# M466_and_M462B_Output_Amplifier.net
KiCad netlist of a schematic drawn in EAGLE
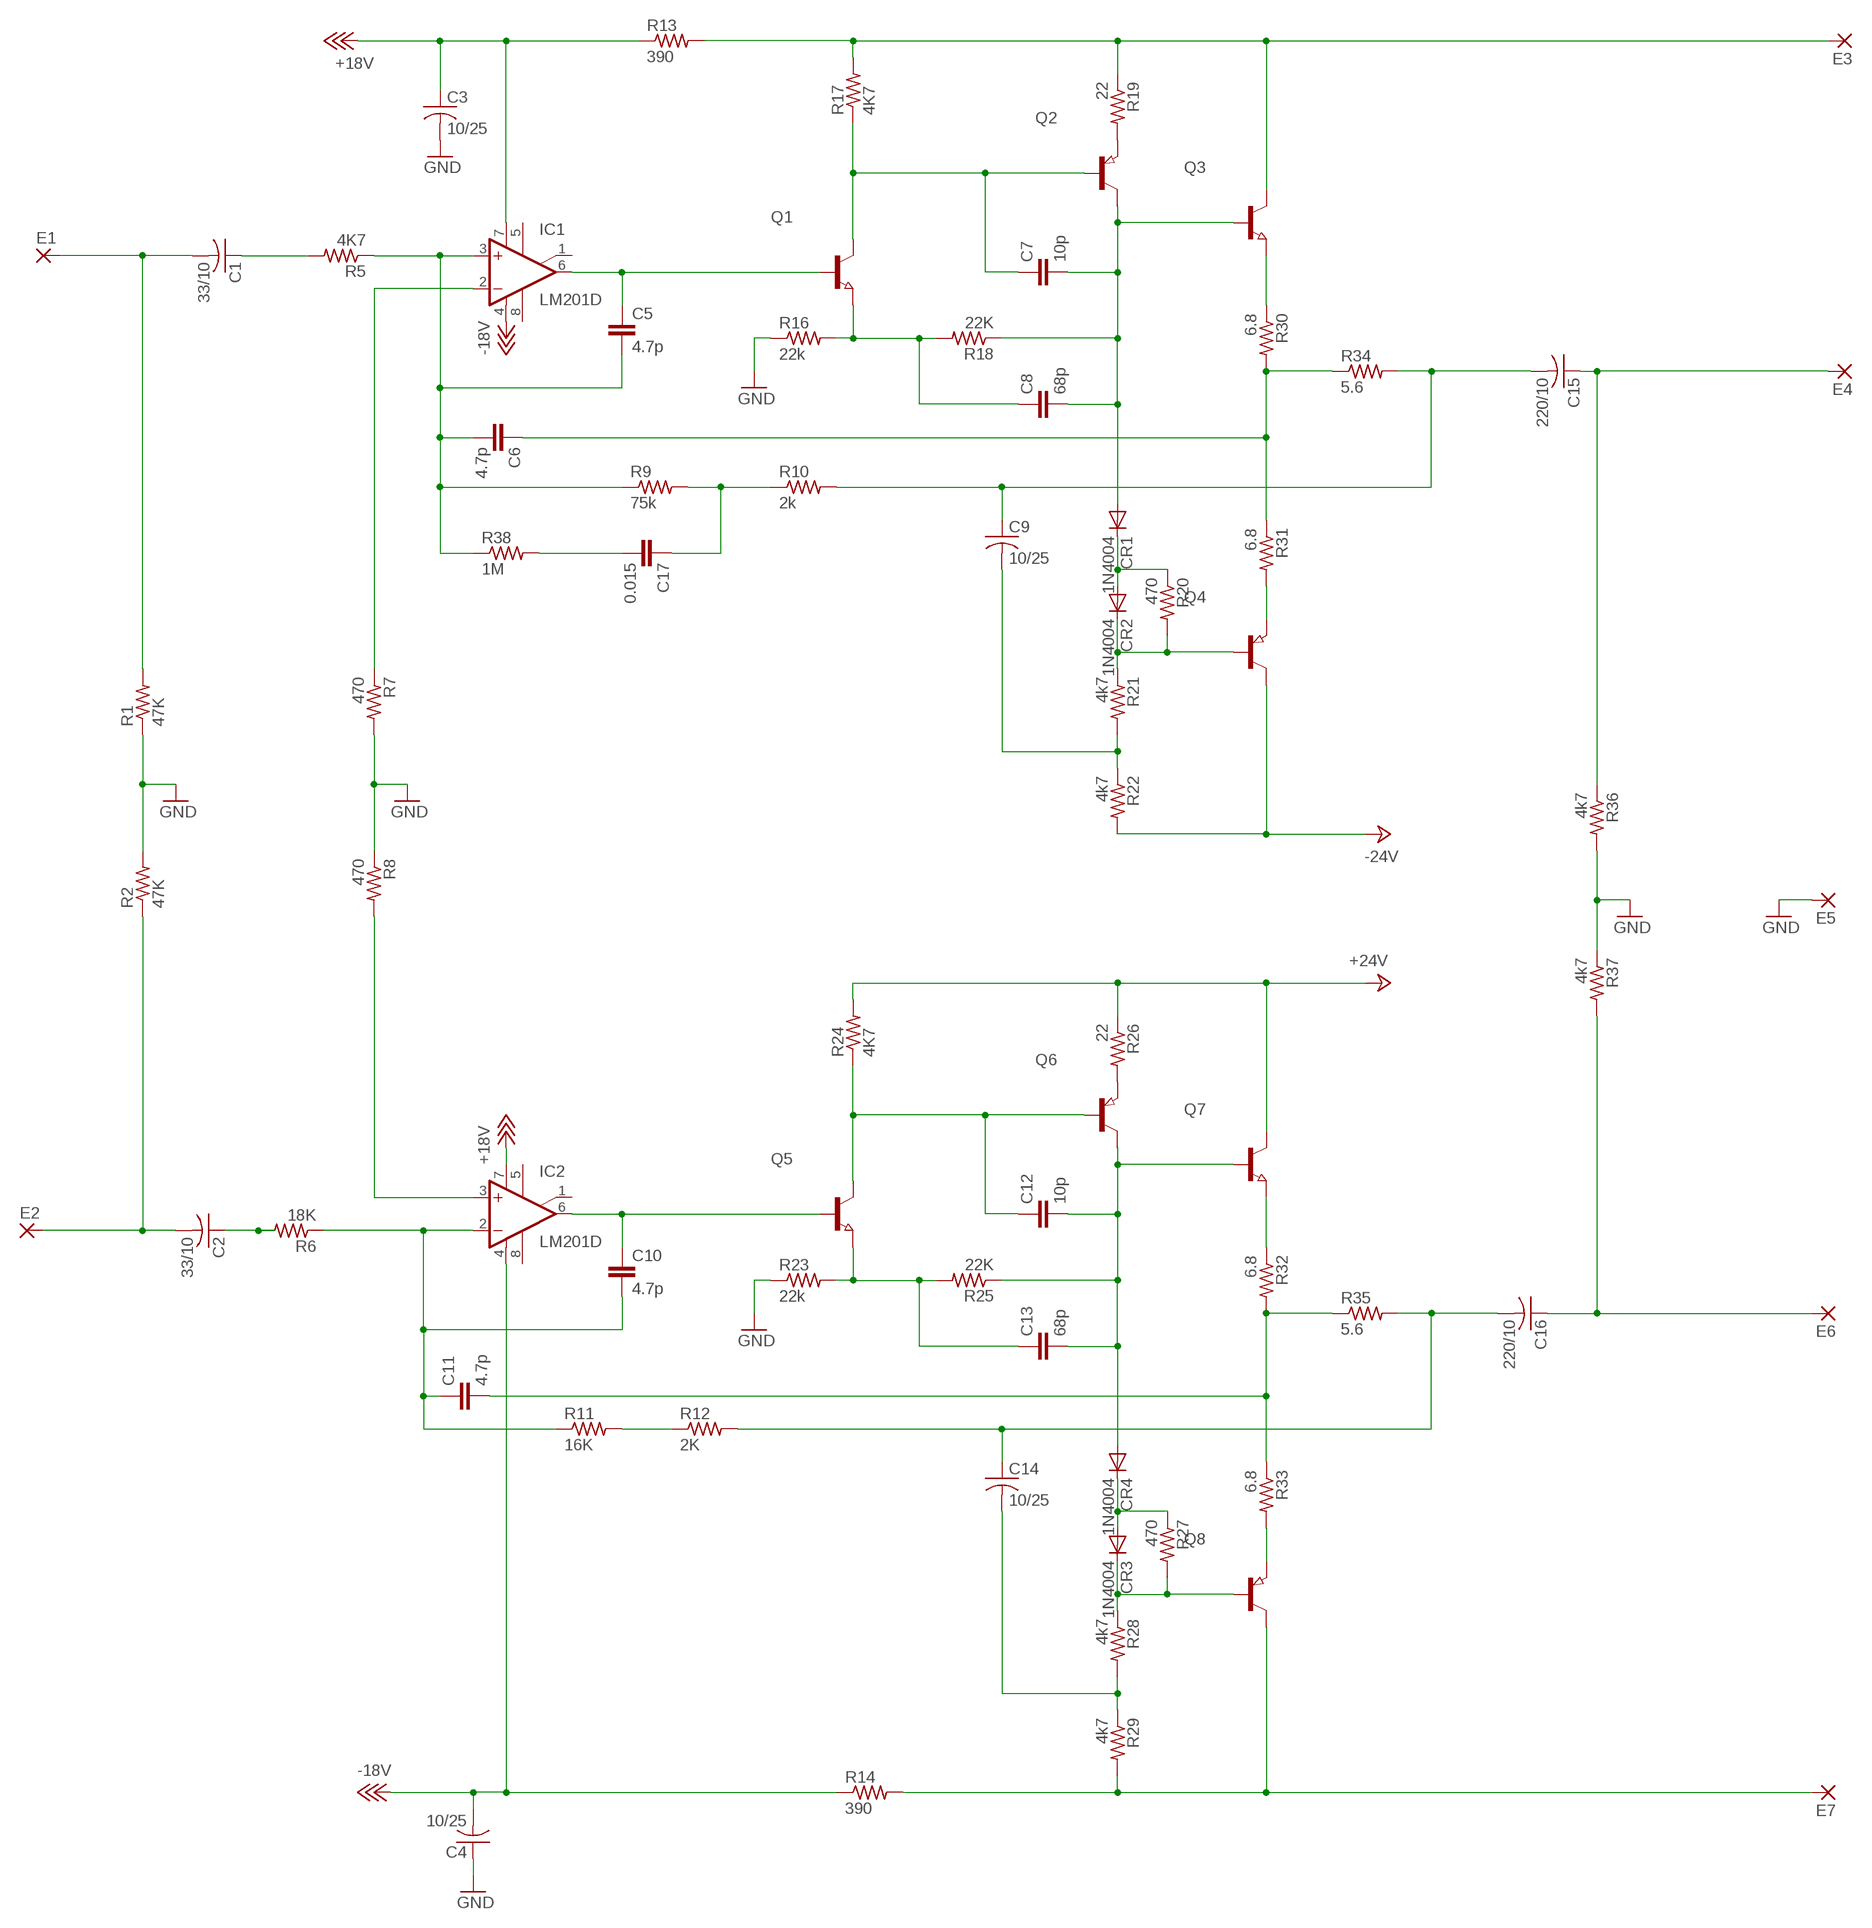
[diagram p0: schematic, sheet 1]

(export (version "E")
  (design (tool "Eeschema 10.0.6"))
  (components
    (comp (ref "C1")
      (value "33/10")
      (footprint "eagle-import:C0805")
      (libsource (lib "eagle-import") (part "C-USC0805"))
    )
    (comp (ref "C2")
      (value "33/10")
      (footprint "eagle-import:C0805")
      (libsource (lib "eagle-import") (part "C-USC0805"))
    )
    (comp (ref "C3")
      (value "10/25")
      (footprint "eagle-import:C0805")
      (libsource (lib "eagle-import") (part "C-USC0805"))
    )
    (comp (ref "C4")
      (value "10/25")
      (footprint "eagle-import:C0805")
      (libsource (lib "eagle-import") (part "C-USC0805"))
    )
    (comp (ref "C5")
      (value "4.7p")
      (footprint "eagle-import:C2.5-5")
      (libsource (lib "eagle-import") (part "C2.5/5"))
    )
    (comp (ref "C6")
      (value "4.7p")
      (footprint "eagle-import:C2.5-5")
      (libsource (lib "eagle-import") (part "C2.5/5"))
    )
    (comp (ref "C7")
      (value "10p")
      (footprint "eagle-import:C2.5-5")
      (libsource (lib "eagle-import") (part "C2.5/5"))
    )
    (comp (ref "C8")
      (value "68p")
      (footprint "eagle-import:C2.5-5")
      (libsource (lib "eagle-import") (part "C2.5/5"))
    )
    (comp (ref "C9")
      (value "10/25")
      (footprint "eagle-import:C0805")
      (libsource (lib "eagle-import") (part "C-USC0805"))
    )
    (comp (ref "C10")
      (value "4.7p")
      (footprint "eagle-import:C2.5-5")
      (libsource (lib "eagle-import") (part "C2.5/5"))
    )
    (comp (ref "C11")
      (value "4.7p")
      (footprint "eagle-import:C2.5-5")
      (libsource (lib "eagle-import") (part "C2.5/5"))
    )
    (comp (ref "C12")
      (value "10p")
      (footprint "eagle-import:C2.5-5")
      (libsource (lib "eagle-import") (part "C2.5/5"))
    )
    (comp (ref "C13")
      (value "68p")
      (footprint "eagle-import:C2.5-5")
      (libsource (lib "eagle-import") (part "C2.5/5"))
    )
    (comp (ref "C14")
      (value "10/25")
      (footprint "eagle-import:C0805")
      (libsource (lib "eagle-import") (part "C-USC0805"))
    )
    (comp (ref "C15")
      (value "220/10")
      (footprint "eagle-import:C0805")
      (libsource (lib "eagle-import") (part "C-USC0805"))
    )
    (comp (ref "C16")
      (value "220/10")
      (footprint "eagle-import:C0805")
      (libsource (lib "eagle-import") (part "C-USC0805"))
    )
    (comp (ref "C17")
      (value "0.015")
      (footprint "eagle-import:C2.5-5")
      (libsource (lib "eagle-import") (part "C2.5/5"))
    )
    (comp (ref "CR1")
      (value "1N4004")
      (footprint "eagle-import:DO41-10")
      (libsource (lib "eagle-import") (part "1N4004"))
    )
    (comp (ref "CR2")
      (value "1N4004")
      (footprint "eagle-import:DO41-10")
      (libsource (lib "eagle-import") (part "1N4004"))
    )
    (comp (ref "CR3")
      (value "1N4004")
      (footprint "eagle-import:DO41-10")
      (libsource (lib "eagle-import") (part "1N4004"))
    )
    (comp (ref "CR4")
      (value "1N4004")
      (footprint "eagle-import:DO41-10")
      (libsource (lib "eagle-import") (part "1N4004"))
    )
    (comp (ref "E1")
      (value "SMD2")
      (footprint "eagle-import:SMD1,27-2,54")
      (libsource (lib "eagle-import") (part "SMD2"))
    )
    (comp (ref "E2")
      (value "SMD2")
      (footprint "eagle-import:SMD1,27-2,54")
      (libsource (lib "eagle-import") (part "SMD2"))
    )
    (comp (ref "E3")
      (value "SMD2")
      (footprint "eagle-import:SMD1,27-2,54")
      (libsource (lib "eagle-import") (part "SMD2"))
    )
    (comp (ref "E4")
      (value "SMD2")
      (footprint "eagle-import:SMD1,27-2,54")
      (libsource (lib "eagle-import") (part "SMD2"))
    )
    (comp (ref "E5")
      (value "SMD2")
      (footprint "eagle-import:SMD1,27-2,54")
      (libsource (lib "eagle-import") (part "SMD2"))
    )
    (comp (ref "E6")
      (value "SMD2")
      (footprint "eagle-import:SMD1,27-2,54")
      (libsource (lib "eagle-import") (part "SMD2"))
    )
    (comp (ref "E7")
      (value "SMD2")
      (footprint "eagle-import:SMD1,27-2,54")
      (libsource (lib "eagle-import") (part "SMD2"))
    )
    (comp (ref "IC1")
      (value "LM201D")
      (footprint "eagle-import:SO08")
      (libsource (lib "eagle-import") (part "LM201D"))
    )
    (comp (ref "IC2")
      (value "LM201D")
      (footprint "eagle-import:SO08")
      (libsource (lib "eagle-import") (part "LM201D"))
    )
    (comp (ref "Q1")
      (value "NPN-TRANSISTOR_SOT23")
      (footprint "eagle-import:SOT23")
      (libsource (lib "eagle-import") (part "NPN-TRANSISTOR_SOT23"))
    )
    (comp (ref "Q2")
      (value "PNP-TRANSISTOR_SOT23")
      (footprint "eagle-import:SOT23")
      (libsource (lib "eagle-import") (part "PNP-TRANSISTOR_SOT23"))
    )
    (comp (ref "Q3")
      (value "NPN-TRANSISTOR_SOT23")
      (footprint "eagle-import:SOT23")
      (libsource (lib "eagle-import") (part "NPN-TRANSISTOR_SOT23"))
    )
    (comp (ref "Q4")
      (value "PNP-TRANSISTOR_SOT23")
      (footprint "eagle-import:SOT23")
      (libsource (lib "eagle-import") (part "PNP-TRANSISTOR_SOT23"))
    )
    (comp (ref "Q5")
      (value "NPN-TRANSISTOR_SOT23")
      (footprint "eagle-import:SOT23")
      (libsource (lib "eagle-import") (part "NPN-TRANSISTOR_SOT23"))
    )
    (comp (ref "Q6")
      (value "PNP-TRANSISTOR_SOT23")
      (footprint "eagle-import:SOT23")
      (libsource (lib "eagle-import") (part "PNP-TRANSISTOR_SOT23"))
    )
    (comp (ref "Q7")
      (value "NPN-TRANSISTOR_SOT23")
      (footprint "eagle-import:SOT23")
      (libsource (lib "eagle-import") (part "NPN-TRANSISTOR_SOT23"))
    )
    (comp (ref "Q8")
      (value "PNP-TRANSISTOR_SOT23")
      (footprint "eagle-import:SOT23")
      (libsource (lib "eagle-import") (part "PNP-TRANSISTOR_SOT23"))
    )
    (comp (ref "R1")
      (value "47K")
      (footprint "eagle-import:R0805")
      (libsource (lib "eagle-import") (part "R-US_R0805"))
    )
    (comp (ref "R2")
      (value "47K")
      (footprint "eagle-import:R0805")
      (libsource (lib "eagle-import") (part "R-US_R0805"))
    )
    (comp (ref "R5")
      (value "4K7")
      (footprint "eagle-import:R0805")
      (libsource (lib "eagle-import") (part "R-US_R0805"))
    )
    (comp (ref "R6")
      (value "18K")
      (footprint "eagle-import:R0805")
      (libsource (lib "eagle-import") (part "R-US_R0805"))
    )
    (comp (ref "R7")
      (value "470")
      (footprint "eagle-import:R0805")
      (libsource (lib "eagle-import") (part "R-US_R0805"))
    )
    (comp (ref "R8")
      (value "470")
      (footprint "eagle-import:R0805")
      (libsource (lib "eagle-import") (part "R-US_R0805"))
    )
    (comp (ref "R9")
      (value "75k")
      (footprint "eagle-import:R0805")
      (libsource (lib "eagle-import") (part "R-US_R0805"))
    )
    (comp (ref "R10")
      (value "2k")
      (footprint "eagle-import:R0805")
      (libsource (lib "eagle-import") (part "R-US_R0805"))
    )
    (comp (ref "R11")
      (value "16K")
      (footprint "eagle-import:R0805")
      (libsource (lib "eagle-import") (part "R-US_R0805"))
    )
    (comp (ref "R12")
      (value "2K")
      (footprint "eagle-import:R0805")
      (libsource (lib "eagle-import") (part "R-US_R0805"))
    )
    (comp (ref "R13")
      (value "390")
      (footprint "eagle-import:R0805")
      (libsource (lib "eagle-import") (part "R-US_R0805"))
    )
    (comp (ref "R14")
      (value "390")
      (footprint "eagle-import:R0805")
      (libsource (lib "eagle-import") (part "R-US_R0805"))
    )
    (comp (ref "R16")
      (value "22k")
      (footprint "eagle-import:R0805")
      (libsource (lib "eagle-import") (part "R-US_R0805"))
    )
    (comp (ref "R17")
      (value "4K7")
      (footprint "eagle-import:R0805")
      (libsource (lib "eagle-import") (part "R-US_R0805"))
    )
    (comp (ref "R18")
      (value "22K")
      (footprint "eagle-import:R0805")
      (libsource (lib "eagle-import") (part "R-US_R0805"))
    )
    (comp (ref "R19")
      (value "22")
      (footprint "eagle-import:R0805")
      (libsource (lib "eagle-import") (part "R-US_R0805"))
    )
    (comp (ref "R20")
      (value "470")
      (footprint "eagle-import:R0805")
      (libsource (lib "eagle-import") (part "R-US_R0805"))
    )
    (comp (ref "R21")
      (value "4k7")
      (footprint "eagle-import:R0805")
      (libsource (lib "eagle-import") (part "R-US_R0805"))
    )
    (comp (ref "R22")
      (value "4k7")
      (footprint "eagle-import:R0805")
      (libsource (lib "eagle-import") (part "R-US_R0805"))
    )
    (comp (ref "R23")
      (value "22k")
      (footprint "eagle-import:R0805")
      (libsource (lib "eagle-import") (part "R-US_R0805"))
    )
    (comp (ref "R24")
      (value "4K7")
      (footprint "eagle-import:R0805")
      (libsource (lib "eagle-import") (part "R-US_R0805"))
    )
    (comp (ref "R25")
      (value "22K")
      (footprint "eagle-import:R0805")
      (libsource (lib "eagle-import") (part "R-US_R0805"))
    )
    (comp (ref "R26")
      (value "22")
      (footprint "eagle-import:R0805")
      (libsource (lib "eagle-import") (part "R-US_R0805"))
    )
    (comp (ref "R27")
      (value "470")
      (footprint "eagle-import:R0805")
      (libsource (lib "eagle-import") (part "R-US_R0805"))
    )
    (comp (ref "R28")
      (value "4k7")
      (footprint "eagle-import:R0805")
      (libsource (lib "eagle-import") (part "R-US_R0805"))
    )
    (comp (ref "R29")
      (value "4k7")
      (footprint "eagle-import:R0805")
      (libsource (lib "eagle-import") (part "R-US_R0805"))
    )
    (comp (ref "R30")
      (value "6.8")
      (footprint "eagle-import:R0805")
      (libsource (lib "eagle-import") (part "R-US_R0805"))
    )
    (comp (ref "R31")
      (value "6.8")
      (footprint "eagle-import:R0805")
      (libsource (lib "eagle-import") (part "R-US_R0805"))
    )
    (comp (ref "R32")
      (value "6.8")
      (footprint "eagle-import:R0805")
      (libsource (lib "eagle-import") (part "R-US_R0805"))
    )
    (comp (ref "R33")
      (value "6.8")
      (footprint "eagle-import:R0805")
      (libsource (lib "eagle-import") (part "R-US_R0805"))
    )
    (comp (ref "R34")
      (value "5.6")
      (footprint "eagle-import:R0805")
      (libsource (lib "eagle-import") (part "R-US_R0805"))
    )
    (comp (ref "R35")
      (value "5.6")
      (footprint "eagle-import:R0805")
      (libsource (lib "eagle-import") (part "R-US_R0805"))
    )
    (comp (ref "R36")
      (value "4k7")
      (footprint "eagle-import:R0805")
      (libsource (lib "eagle-import") (part "R-US_R0805"))
    )
    (comp (ref "R37")
      (value "4k7")
      (footprint "eagle-import:R0805")
      (libsource (lib "eagle-import") (part "R-US_R0805"))
    )
    (comp (ref "R38")
      (value "1M")
      (footprint "eagle-import:R0805")
      (libsource (lib "eagle-import") (part "R-US_R0805"))
    )
  )
  (nets
    (net (code "1") (name "+18V") (class "Default")
      (node (ref "C3") (pin "1") (pinfunction "1_1") (pintype "passive"))
      (node (ref "IC1") (pin "7") (pinfunction "V+_7") (pintype "power_in"))
      (node (ref "IC2") (pin "7") (pinfunction "V+_7") (pintype "power_in"))
      (node (ref "R13") (pin "1") (pinfunction "1_1") (pintype "passive"))
    )
    (net (code "2") (name "+24V") (class "Default")
      (node (ref "Q7") (pin "3") (pinfunction "C_3") (pintype "passive"))
      (node (ref "R24") (pin "2") (pinfunction "2_2") (pintype "passive"))
      (node (ref "R26") (pin "1") (pinfunction "1_1") (pintype "passive"))
    )
    (net (code "3") (name "-18V") (class "Default")
      (node (ref "C4") (pin "2") (pinfunction "2_2") (pintype "passive"))
      (node (ref "IC1") (pin "4") (pinfunction "V-_4") (pintype "power_in"))
      (node (ref "IC2") (pin "4") (pinfunction "V-_4") (pintype "power_in"))
      (node (ref "R14") (pin "1") (pinfunction "1_1") (pintype "passive"))
    )
    (net (code "4") (name "-24V") (class "Default")
      (node (ref "Q4") (pin "3") (pinfunction "C_3") (pintype "passive"))
      (node (ref "R22") (pin "2") (pinfunction "2_2") (pintype "passive"))
    )
    (net (code "5") (name "GND") (class "Default")
      (node (ref "C3") (pin "2") (pinfunction "2_2") (pintype "passive"))
      (node (ref "C4") (pin "1") (pinfunction "1_1") (pintype "passive"))
      (node (ref "E5") (pin "1") (pinfunction "P_1") (pintype "passive"))
      (node (ref "R1") (pin "1") (pinfunction "1_1") (pintype "passive"))
      (node (ref "R16") (pin "1") (pinfunction "1_1") (pintype "passive"))
      (node (ref "R2") (pin "2") (pinfunction "2_2") (pintype "passive"))
      (node (ref "R23") (pin "1") (pinfunction "1_1") (pintype "passive"))
      (node (ref "R36") (pin "2") (pinfunction "2_2") (pintype "passive"))
      (node (ref "R37") (pin "1") (pinfunction "1_1") (pintype "passive"))
      (node (ref "R7") (pin "2") (pinfunction "2_2") (pintype "passive"))
      (node (ref "R8") (pin "1") (pinfunction "1_1") (pintype "passive"))
    )
    (net (code "6") (name "Net-(C1-Pad1)") (class "Default")
      (node (ref "C1") (pin "1") (pinfunction "1_1") (pintype "passive"))
      (node (ref "R5") (pin "2") (pinfunction "2_2") (pintype "passive"))
    )
    (net (code "7") (name "Net-(C2-Pad1)") (class "Default")
      (node (ref "C2") (pin "1") (pinfunction "1_1") (pintype "passive"))
      (node (ref "R6") (pin "2") (pinfunction "2_2") (pintype "passive"))
    )
    (net (code "8") (name "Net-(C6-Pad1)") (class "Default")
      (node (ref "C6") (pin "1") (pinfunction "1_1") (pintype "passive"))
      (node (ref "R30") (pin "2") (pinfunction "2_2") (pintype "passive"))
      (node (ref "R31") (pin "1") (pinfunction "1_1") (pintype "passive"))
      (node (ref "R34") (pin "1") (pinfunction "1_1") (pintype "passive"))
    )
    (net (code "9") (name "Net-(C9-Pad2)") (class "Default")
      (node (ref "C9") (pin "2") (pinfunction "2_2") (pintype "passive"))
      (node (ref "R21") (pin "2") (pinfunction "2_2") (pintype "passive"))
      (node (ref "R22") (pin "1") (pinfunction "1_1") (pintype "passive"))
    )
    (net (code "10") (name "Net-(C11-Pad2)") (class "Default")
      (node (ref "C11") (pin "2") (pinfunction "2_2") (pintype "passive"))
      (node (ref "R32") (pin "2") (pinfunction "2_2") (pintype "passive"))
      (node (ref "R33") (pin "1") (pinfunction "1_1") (pintype "passive"))
      (node (ref "R35") (pin "1") (pinfunction "1_1") (pintype "passive"))
    )
    (net (code "11") (name "Net-(C14-Pad1)") (class "Default")
      (node (ref "C14") (pin "1") (pinfunction "1_1") (pintype "passive"))
      (node (ref "C16") (pin "2") (pinfunction "2_2") (pintype "passive"))
      (node (ref "R12") (pin "2") (pinfunction "2_2") (pintype "passive"))
      (node (ref "R35") (pin "2") (pinfunction "2_2") (pintype "passive"))
    )
    (net (code "12") (name "Net-(C14-Pad2)") (class "Default")
      (node (ref "C14") (pin "2") (pinfunction "2_2") (pintype "passive"))
      (node (ref "R28") (pin "2") (pinfunction "2_2") (pintype "passive"))
      (node (ref "R29") (pin "1") (pinfunction "1_1") (pintype "passive"))
    )
    (net (code "13") (name "Net-(C15-Pad2)") (class "Default")
      (node (ref "C15") (pin "2") (pinfunction "2_2") (pintype "passive"))
      (node (ref "C9") (pin "1") (pinfunction "1_1") (pintype "passive"))
      (node (ref "R10") (pin "2") (pinfunction "2_2") (pintype "passive"))
      (node (ref "R34") (pin "2") (pinfunction "2_2") (pintype "passive"))
    )
    (net (code "14") (name "Net-(C17-Pad1)") (class "Default")
      (node (ref "C17") (pin "1") (pinfunction "1_1") (pintype "passive"))
      (node (ref "R10") (pin "1") (pinfunction "1_1") (pintype "passive"))
      (node (ref "R9") (pin "2") (pinfunction "2_2") (pintype "passive"))
    )
    (net (code "15") (name "Net-(C17-Pad2)") (class "Default")
      (node (ref "C17") (pin "2") (pinfunction "2_2") (pintype "passive"))
      (node (ref "R38") (pin "2") (pinfunction "2_2") (pintype "passive"))
    )
    (net (code "16") (name "Net-(CR1-PadC)") (class "Default")
      (node (ref "CR1") (pin "C") (pinfunction "C_C") (pintype "passive"))
      (node (ref "CR2") (pin "A") (pinfunction "A_A") (pintype "passive"))
      (node (ref "R20") (pin "1") (pinfunction "1_1") (pintype "passive"))
    )
    (net (code "17") (name "Net-(CR3-PadA)") (class "Default")
      (node (ref "CR3") (pin "A") (pinfunction "A_A") (pintype "passive"))
      (node (ref "CR4") (pin "C") (pinfunction "C_C") (pintype "passive"))
      (node (ref "R27") (pin "1") (pinfunction "1_1") (pintype "passive"))
    )
    (net (code "18") (name "Net-(E1-P)") (class "Default")
      (node (ref "C1") (pin "2") (pinfunction "2_2") (pintype "passive"))
      (node (ref "E1") (pin "1") (pinfunction "P_1") (pintype "passive"))
      (node (ref "R1") (pin "2") (pinfunction "2_2") (pintype "passive"))
    )
    (net (code "19") (name "Net-(E2-P)") (class "Default")
      (node (ref "C2") (pin "2") (pinfunction "2_2") (pintype "passive"))
      (node (ref "E2") (pin "1") (pinfunction "P_1") (pintype "passive"))
      (node (ref "R2") (pin "1") (pinfunction "1_1") (pintype "passive"))
    )
    (net (code "20") (name "Net-(E3-P)") (class "Default")
      (node (ref "E3") (pin "1") (pinfunction "P_1") (pintype "passive"))
      (node (ref "Q3") (pin "3") (pinfunction "C_3") (pintype "passive"))
      (node (ref "R13") (pin "2") (pinfunction "2_2") (pintype "passive"))
      (node (ref "R17") (pin "2") (pinfunction "2_2") (pintype "passive"))
      (node (ref "R19") (pin "1") (pinfunction "1_1") (pintype "passive"))
    )
    (net (code "21") (name "Net-(E4-P)") (class "Default")
      (node (ref "C15") (pin "1") (pinfunction "1_1") (pintype "passive"))
      (node (ref "E4") (pin "1") (pinfunction "P_1") (pintype "passive"))
      (node (ref "R36") (pin "1") (pinfunction "1_1") (pintype "passive"))
    )
    (net (code "22") (name "Net-(E6-P)") (class "Default")
      (node (ref "C16") (pin "1") (pinfunction "1_1") (pintype "passive"))
      (node (ref "E6") (pin "1") (pinfunction "P_1") (pintype "passive"))
      (node (ref "R37") (pin "2") (pinfunction "2_2") (pintype "passive"))
    )
    (net (code "23") (name "Net-(E7-P)") (class "Default")
      (node (ref "E7") (pin "1") (pinfunction "P_1") (pintype "passive"))
      (node (ref "Q8") (pin "3") (pinfunction "C_3") (pintype "passive"))
      (node (ref "R14") (pin "2") (pinfunction "2_2") (pintype "passive"))
      (node (ref "R29") (pin "2") (pinfunction "2_2") (pintype "passive"))
    )
    (net (code "24") (name "Net-(IC1-+IN)") (class "Default")
      (node (ref "C5") (pin "2") (pinfunction "2_2") (pintype "passive"))
      (node (ref "C6") (pin "2") (pinfunction "2_2") (pintype "passive"))
      (node (ref "IC1") (pin "3") (pinfunction "+IN_3") (pintype "input"))
      (node (ref "R38") (pin "1") (pinfunction "1_1") (pintype "passive"))
      (node (ref "R5") (pin "1") (pinfunction "1_1") (pintype "passive"))
      (node (ref "R9") (pin "1") (pinfunction "1_1") (pintype "passive"))
    )
    (net (code "25") (name "Net-(IC1--IN)") (class "Default")
      (node (ref "IC1") (pin "2") (pinfunction "-IN_2") (pintype "input"))
      (node (ref "R7") (pin "1") (pinfunction "1_1") (pintype "passive"))
    )
    (net (code "26") (name "Net-(IC1-OUT)") (class "Default")
      (node (ref "C5") (pin "1") (pinfunction "1_1") (pintype "passive"))
      (node (ref "IC1") (pin "6") (pinfunction "OUT_6") (pintype "output"))
      (node (ref "Q1") (pin "1") (pinfunction "B_1") (pintype "passive"))
    )
    (net (code "27") (name "Net-(IC2-+IN)") (class "Default")
      (node (ref "IC2") (pin "3") (pinfunction "+IN_3") (pintype "input"))
      (node (ref "R8") (pin "2") (pinfunction "2_2") (pintype "passive"))
    )
    (net (code "28") (name "Net-(IC2--IN)") (class "Default")
      (node (ref "C10") (pin "2") (pinfunction "2_2") (pintype "passive"))
      (node (ref "C11") (pin "1") (pinfunction "1_1") (pintype "passive"))
      (node (ref "IC2") (pin "2") (pinfunction "-IN_2") (pintype "input"))
      (node (ref "R11") (pin "1") (pinfunction "1_1") (pintype "passive"))
      (node (ref "R6") (pin "1") (pinfunction "1_1") (pintype "passive"))
    )
    (net (code "29") (name "Net-(IC2-OUT)") (class "Default")
      (node (ref "C10") (pin "1") (pinfunction "1_1") (pintype "passive"))
      (node (ref "IC2") (pin "6") (pinfunction "OUT_6") (pintype "output"))
      (node (ref "Q5") (pin "1") (pinfunction "B_1") (pintype "passive"))
    )
    (net (code "30") (name "Net-(Q1-C)") (class "Default")
      (node (ref "C7") (pin "1") (pinfunction "1_1") (pintype "passive"))
      (node (ref "Q1") (pin "3") (pinfunction "C_3") (pintype "passive"))
      (node (ref "Q2") (pin "1") (pinfunction "B_1") (pintype "passive"))
      (node (ref "R17") (pin "1") (pinfunction "1_1") (pintype "passive"))
    )
    (net (code "31") (name "Net-(Q1-E)") (class "Default")
      (node (ref "C8") (pin "1") (pinfunction "1_1") (pintype "passive"))
      (node (ref "Q1") (pin "2") (pinfunction "E_2") (pintype "passive"))
      (node (ref "R16") (pin "2") (pinfunction "2_2") (pintype "passive"))
      (node (ref "R18") (pin "2") (pinfunction "2_2") (pintype "passive"))
    )
    (net (code "32") (name "Net-(Q2-C)") (class "Default")
      (node (ref "C7") (pin "2") (pinfunction "2_2") (pintype "passive"))
      (node (ref "C8") (pin "2") (pinfunction "2_2") (pintype "passive"))
      (node (ref "CR1") (pin "A") (pinfunction "A_A") (pintype "passive"))
      (node (ref "Q2") (pin "3") (pinfunction "C_3") (pintype "passive"))
      (node (ref "Q3") (pin "1") (pinfunction "B_1") (pintype "passive"))
      (node (ref "R18") (pin "1") (pinfunction "1_1") (pintype "passive"))
    )
    (net (code "33") (name "Net-(Q2-E)") (class "Default")
      (node (ref "Q2") (pin "2") (pinfunction "E_2") (pintype "passive"))
      (node (ref "R19") (pin "2") (pinfunction "2_2") (pintype "passive"))
    )
    (net (code "34") (name "Net-(Q3-E)") (class "Default")
      (node (ref "Q3") (pin "2") (pinfunction "E_2") (pintype "passive"))
      (node (ref "R30") (pin "1") (pinfunction "1_1") (pintype "passive"))
    )
    (net (code "35") (name "Net-(Q4-B)") (class "Default")
      (node (ref "CR2") (pin "C") (pinfunction "C_C") (pintype "passive"))
      (node (ref "Q4") (pin "1") (pinfunction "B_1") (pintype "passive"))
      (node (ref "R20") (pin "2") (pinfunction "2_2") (pintype "passive"))
      (node (ref "R21") (pin "1") (pinfunction "1_1") (pintype "passive"))
    )
    (net (code "36") (name "Net-(Q4-E)") (class "Default")
      (node (ref "Q4") (pin "2") (pinfunction "E_2") (pintype "passive"))
      (node (ref "R31") (pin "2") (pinfunction "2_2") (pintype "passive"))
    )
    (net (code "37") (name "Net-(Q5-C)") (class "Default")
      (node (ref "C12") (pin "1") (pinfunction "1_1") (pintype "passive"))
      (node (ref "Q5") (pin "3") (pinfunction "C_3") (pintype "passive"))
      (node (ref "Q6") (pin "1") (pinfunction "B_1") (pintype "passive"))
      (node (ref "R24") (pin "1") (pinfunction "1_1") (pintype "passive"))
    )
    (net (code "38") (name "Net-(Q5-E)") (class "Default")
      (node (ref "C13") (pin "1") (pinfunction "1_1") (pintype "passive"))
      (node (ref "Q5") (pin "2") (pinfunction "E_2") (pintype "passive"))
      (node (ref "R23") (pin "2") (pinfunction "2_2") (pintype "passive"))
      (node (ref "R25") (pin "2") (pinfunction "2_2") (pintype "passive"))
    )
    (net (code "39") (name "Net-(Q6-C)") (class "Default")
      (node (ref "C12") (pin "2") (pinfunction "2_2") (pintype "passive"))
      (node (ref "C13") (pin "2") (pinfunction "2_2") (pintype "passive"))
      (node (ref "CR4") (pin "A") (pinfunction "A_A") (pintype "passive"))
      (node (ref "Q6") (pin "3") (pinfunction "C_3") (pintype "passive"))
      (node (ref "Q7") (pin "1") (pinfunction "B_1") (pintype "passive"))
      (node (ref "R25") (pin "1") (pinfunction "1_1") (pintype "passive"))
    )
    (net (code "40") (name "Net-(Q6-E)") (class "Default")
      (node (ref "Q6") (pin "2") (pinfunction "E_2") (pintype "passive"))
      (node (ref "R26") (pin "2") (pinfunction "2_2") (pintype "passive"))
    )
    (net (code "41") (name "Net-(Q7-E)") (class "Default")
      (node (ref "Q7") (pin "2") (pinfunction "E_2") (pintype "passive"))
      (node (ref "R32") (pin "1") (pinfunction "1_1") (pintype "passive"))
    )
    (net (code "42") (name "Net-(Q8-B)") (class "Default")
      (node (ref "CR3") (pin "C") (pinfunction "C_C") (pintype "passive"))
      (node (ref "Q8") (pin "1") (pinfunction "B_1") (pintype "passive"))
      (node (ref "R27") (pin "2") (pinfunction "2_2") (pintype "passive"))
      (node (ref "R28") (pin "1") (pinfunction "1_1") (pintype "passive"))
    )
    (net (code "43") (name "Net-(Q8-E)") (class "Default")
      (node (ref "Q8") (pin "2") (pinfunction "E_2") (pintype "passive"))
      (node (ref "R33") (pin "2") (pinfunction "2_2") (pintype "passive"))
    )
    (net (code "44") (name "Net-(R11-Pad2)") (class "Default")
      (node (ref "R11") (pin "2") (pinfunction "2_2") (pintype "passive"))
      (node (ref "R12") (pin "1") (pinfunction "1_1") (pintype "passive"))
    )
    (net (code "45") (name "unconnected-(IC1-CMP-Pad8)") (class "Default")
      (node (ref "IC1") (pin "8") (pinfunction "CMP_8") (pintype "passive"))
    )
    (net (code "46") (name "unconnected-(IC1-ON-Pad5)") (class "Default")
      (node (ref "IC1") (pin "5") (pinfunction "ON_5") (pintype "passive"))
    )
    (net (code "47") (name "unconnected-(IC1-ON{slash}CMP-Pad1)") (class "Default")
      (node (ref "IC1") (pin "1") (pinfunction "ON/CMP_1") (pintype "passive"))
    )
    (net (code "48") (name "unconnected-(IC2-CMP-Pad8)") (class "Default")
      (node (ref "IC2") (pin "8") (pinfunction "CMP_8") (pintype "passive"))
    )
    (net (code "49") (name "unconnected-(IC2-ON-Pad5)") (class "Default")
      (node (ref "IC2") (pin "5") (pinfunction "ON_5") (pintype "passive"))
    )
    (net (code "50") (name "unconnected-(IC2-ON{slash}CMP-Pad1)") (class "Default")
      (node (ref "IC2") (pin "1") (pinfunction "ON/CMP_1") (pintype "passive"))
    )
  )
)
